# CPU_v3_0.net
KiCad netlist of a schematic drawn in EAGLE
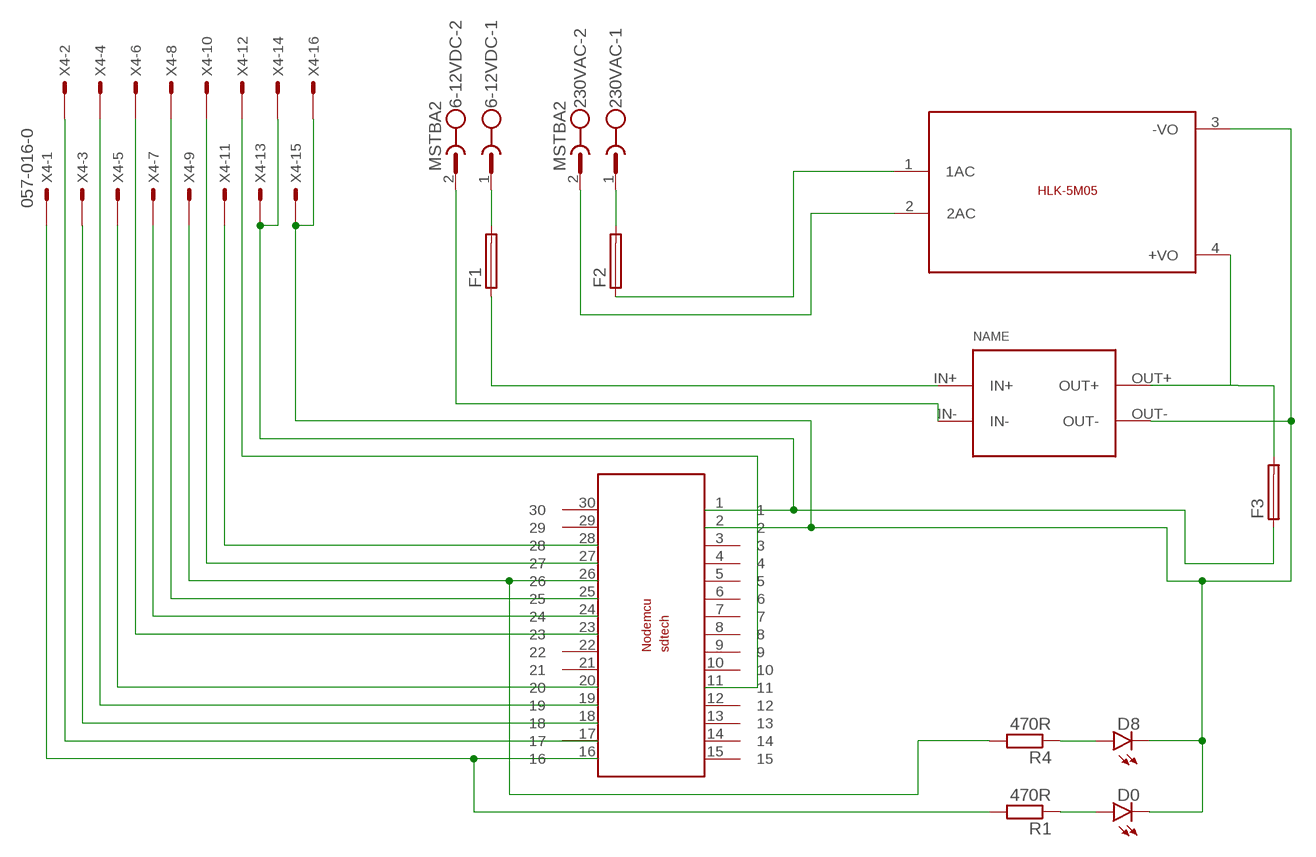
[diagram p0: schematic, sheet 1]

(export (version "E")
  (design (tool "Eeschema 10.0.6"))
  (components
    (comp (ref "6-12VDC")
      (value "MSTBA2")
      (footprint "eagle-import:MSTBA2")
      (fields (field (name "MF") "FARNELL") (field (name "MPN") "1757242"))
      (libsource (lib "eagle-import") (part "MSTBA2"))
    )
    (comp (ref "230VAC")
      (value "MSTBA2")
      (footprint "eagle-import:MSTBA2")
      (fields (field (name "MF") "FARNELL") (field (name "MPN") "1757242"))
      (libsource (lib "eagle-import") (part "MSTBA2"))
    )
    (comp (ref "D0")
      (value "LED3MM")
      (footprint "eagle-import:LED3MM")
      (libsource (lib "eagle-import") (part "LED3MM"))
    )
    (comp (ref "D8")
      (value "LED3MM")
      (footprint "eagle-import:LED3MM")
      (libsource (lib "eagle-import") (part "LED3MM"))
    )
    (comp (ref "F1")
      (value "SH22,5A")
      (footprint "eagle-import:SH22,5A")
      (fields (field (name "MPN") "0031.7701.11"))
      (libsource (lib "eagle-import") (part "SH22,5A"))
    )
    (comp (ref "F2")
      (value "SH22,5A")
      (footprint "eagle-import:SH22,5A")
      (fields (field (name "MPN") "0031.7701.11"))
      (libsource (lib "eagle-import") (part "SH22,5A"))
    )
    (comp (ref "F3")
      (value "SH22,5A")
      (footprint "eagle-import:SH22,5A")
      (fields (field (name "MPN") "0031.7701.11"))
      (libsource (lib "eagle-import") (part "SH22,5A"))
    )
    (comp (ref "R1")
      (value "470R")
      (footprint "eagle-import:0309_10")
      (libsource (lib "eagle-import") (part "R-EU_0309/10"))
    )
    (comp (ref "R4")
      (value "470R")
      (footprint "eagle-import:0309_10")
      (libsource (lib "eagle-import") (part "R-EU_0309/10"))
    )
    (comp (ref "U$1")
      (value "NODEMCUESP8266")
      (footprint "eagle-import:NODEMCUESP8266")
      (fields (field (name "SPICEPREFIX") "X"))
      (libsource (lib "eagle-import") (part "NODEMCUESP8266"))
    )
    (comp (ref "U$2")
      (value "CP8-ADJ")
      (footprint "eagle-import:CP8-ADJ")
      (libsource (lib "eagle-import") (part "CP8-ADJ"))
    )
    (comp (ref "U$3")
      (value "5VDC/5W")
      (footprint "eagle-import:HLK-5M05")
      (libsource (lib "eagle-import") (part "HLK-5M05"))
    )
    (comp (ref "X4")
      (value "057-016-0")
      (footprint "eagle-import:057-016-0")
      (libsource (lib "eagle-import") (part "057-016-0"))
    )
  )
  (nets
    (net (code "1") (name "Net-(6-12VDC-Pad1)") (class "Default")
      (node (ref "6-12VDC") (pin "1") (pinfunction "1_1") (pintype "passive"))
      (node (ref "F1") (pin "2") (pinfunction "2_2") (pintype "passive"))
    )
    (net (code "2") (name "Net-(6-12VDCB-1)") (class "Default")
      (node (ref "6-12VDC") (pin "2") (pinfunction "1_2") (pintype "passive"))
      (node (ref "U$2") (pin "IN-") (pinfunction "IN-_IN-") (pintype "passive"))
    )
    (net (code "3") (name "Net-(230VAC-Pad1)") (class "Default")
      (node (ref "230VAC") (pin "1") (pinfunction "1_1") (pintype "passive"))
      (node (ref "F2") (pin "2") (pinfunction "2_2") (pintype "passive"))
    )
    (net (code "4") (name "Net-(230VACB-1)") (class "Default")
      (node (ref "230VAC") (pin "2") (pinfunction "1_2") (pintype "passive"))
      (node (ref "U$3") (pin "2") (pinfunction "2AC_2") (pintype "bidirectional"))
    )
    (net (code "5") (name "Net-(D0-C)") (class "Default")
      (node (ref "D0") (pin "K") (pinfunction "C_K") (pintype "passive"))
      (node (ref "D8") (pin "K") (pinfunction "C_K") (pintype "passive"))
      (node (ref "U$1") (pin "2") (pinfunction "2_2") (pintype "bidirectional"))
      (node (ref "U$2") (pin "OUT-") (pinfunction "OUT-_OUT-") (pintype "passive"))
      (node (ref "U$3") (pin "3") (pinfunction "-VO_3") (pintype "bidirectional"))
      (node (ref "X4") (pin "15") (pinfunction "S_15") (pintype "passive"))
      (node (ref "X4") (pin "16") (pinfunction "S_16") (pintype "passive"))
    )
    (net (code "6") (name "Net-(D0-PadA)") (class "Default")
      (node (ref "D0") (pin "A") (pinfunction "A_A") (pintype "passive"))
      (node (ref "R1") (pin "1") (pinfunction "1_1") (pintype "passive"))
    )
    (net (code "7") (name "Net-(D8-PadA)") (class "Default")
      (node (ref "D8") (pin "A") (pinfunction "A_A") (pintype "passive"))
      (node (ref "R4") (pin "1") (pinfunction "1_1") (pintype "passive"))
    )
    (net (code "8") (name "Net-(F1-Pad1)") (class "Default")
      (node (ref "F1") (pin "1") (pinfunction "1_1") (pintype "passive"))
      (node (ref "U$2") (pin "IN+") (pinfunction "IN+_IN+") (pintype "passive"))
    )
    (net (code "9") (name "Net-(U$3-+VO)") (class "Default")
      (node (ref "F3") (pin "2") (pinfunction "2_2") (pintype "passive"))
      (node (ref "U$2") (pin "OUT+") (pinfunction "OUT+_OUT+") (pintype "passive"))
      (node (ref "U$3") (pin "4") (pinfunction "+VO_4") (pintype "bidirectional"))
    )
    (net (code "10") (name "Net-(U$3-1AC)") (class "Default")
      (node (ref "F2") (pin "1") (pinfunction "1_1") (pintype "passive"))
      (node (ref "U$3") (pin "1") (pinfunction "1AC_1") (pintype "bidirectional"))
    )
    (net (code "11") (name "Net-(X4A-S)") (class "Default")
      (node (ref "R1") (pin "2") (pinfunction "2_2") (pintype "passive"))
      (node (ref "U$1") (pin "16") (pinfunction "16_16") (pintype "bidirectional"))
      (node (ref "X4") (pin "1") (pinfunction "S_1") (pintype "passive"))
    )
    (net (code "12") (name "Net-(X4B-S)") (class "Default")
      (node (ref "U$1") (pin "27") (pinfunction "27_27") (pintype "bidirectional"))
      (node (ref "X4") (pin "10") (pinfunction "S_10") (pintype "passive"))
    )
    (net (code "13") (name "Net-(X4C-S)") (class "Default")
      (node (ref "U$1") (pin "28") (pinfunction "28_28") (pintype "bidirectional"))
      (node (ref "X4") (pin "11") (pinfunction "S_11") (pintype "passive"))
    )
    (net (code "14") (name "Net-(X4D-S)") (class "Default")
      (node (ref "U$1") (pin "11") (pinfunction "11_11") (pintype "bidirectional"))
      (node (ref "X4") (pin "12") (pinfunction "S_12") (pintype "passive"))
    )
    (net (code "15") (name "Net-(X4E-S)") (class "Default")
      (node (ref "F3") (pin "1") (pinfunction "1_1") (pintype "passive"))
      (node (ref "U$1") (pin "1") (pinfunction "1_1") (pintype "bidirectional"))
      (node (ref "X4") (pin "13") (pinfunction "S_13") (pintype "passive"))
      (node (ref "X4") (pin "14") (pinfunction "S_14") (pintype "passive"))
    )
    (net (code "16") (name "Net-(X4I-S)") (class "Default")
      (node (ref "U$1") (pin "17") (pinfunction "17_17") (pintype "bidirectional"))
      (node (ref "X4") (pin "2") (pinfunction "S_2") (pintype "passive"))
    )
    (net (code "17") (name "Net-(X4J-S)") (class "Default")
      (node (ref "U$1") (pin "18") (pinfunction "18_18") (pintype "bidirectional"))
      (node (ref "X4") (pin "3") (pinfunction "S_3") (pintype "passive"))
    )
    (net (code "18") (name "Net-(X4K-S)") (class "Default")
      (node (ref "U$1") (pin "19") (pinfunction "19_19") (pintype "bidirectional"))
      (node (ref "X4") (pin "4") (pinfunction "S_4") (pintype "passive"))
    )
    (net (code "19") (name "Net-(X4L-S)") (class "Default")
      (node (ref "U$1") (pin "20") (pinfunction "20_20") (pintype "bidirectional"))
      (node (ref "X4") (pin "5") (pinfunction "S_5") (pintype "passive"))
    )
    (net (code "20") (name "Net-(X4M-S)") (class "Default")
      (node (ref "U$1") (pin "23") (pinfunction "23_23") (pintype "bidirectional"))
      (node (ref "X4") (pin "6") (pinfunction "S_6") (pintype "passive"))
    )
    (net (code "21") (name "Net-(X4N-S)") (class "Default")
      (node (ref "U$1") (pin "24") (pinfunction "24_24") (pintype "bidirectional"))
      (node (ref "X4") (pin "7") (pinfunction "S_7") (pintype "passive"))
    )
    (net (code "22") (name "Net-(X4O-S)") (class "Default")
      (node (ref "U$1") (pin "25") (pinfunction "25_25") (pintype "bidirectional"))
      (node (ref "X4") (pin "8") (pinfunction "S_8") (pintype "passive"))
    )
    (net (code "23") (name "Net-(X4P-S)") (class "Default")
      (node (ref "R4") (pin "2") (pinfunction "2_2") (pintype "passive"))
      (node (ref "U$1") (pin "26") (pinfunction "26_26") (pintype "bidirectional"))
      (node (ref "X4") (pin "9") (pinfunction "S_9") (pintype "passive"))
    )
    (net (code "24") (name "unconnected-(U$1-Pad3)") (class "Default")
      (node (ref "U$1") (pin "3") (pinfunction "3_3") (pintype "bidirectional"))
    )
    (net (code "25") (name "unconnected-(U$1-Pad4)") (class "Default")
      (node (ref "U$1") (pin "4") (pinfunction "4_4") (pintype "bidirectional"))
    )
    (net (code "26") (name "unconnected-(U$1-Pad5)") (class "Default")
      (node (ref "U$1") (pin "5") (pinfunction "5_5") (pintype "bidirectional"))
    )
    (net (code "27") (name "unconnected-(U$1-Pad6)") (class "Default")
      (node (ref "U$1") (pin "6") (pinfunction "6_6") (pintype "bidirectional"))
    )
    (net (code "28") (name "unconnected-(U$1-Pad7)") (class "Default")
      (node (ref "U$1") (pin "7") (pinfunction "7_7") (pintype "bidirectional"))
    )
    (net (code "29") (name "unconnected-(U$1-Pad8)") (class "Default")
      (node (ref "U$1") (pin "8") (pinfunction "8_8") (pintype "bidirectional"))
    )
    (net (code "30") (name "unconnected-(U$1-Pad9)") (class "Default")
      (node (ref "U$1") (pin "9") (pinfunction "9_9") (pintype "bidirectional"))
    )
    (net (code "31") (name "unconnected-(U$1-Pad10)") (class "Default")
      (node (ref "U$1") (pin "10") (pinfunction "10_10") (pintype "bidirectional"))
    )
    (net (code "32") (name "unconnected-(U$1-Pad12)") (class "Default")
      (node (ref "U$1") (pin "12") (pinfunction "12_12") (pintype "bidirectional"))
    )
    (net (code "33") (name "unconnected-(U$1-Pad13)") (class "Default")
      (node (ref "U$1") (pin "13") (pinfunction "13_13") (pintype "bidirectional"))
    )
    (net (code "34") (name "unconnected-(U$1-Pad14)") (class "Default")
      (node (ref "U$1") (pin "14") (pinfunction "14_14") (pintype "bidirectional"))
    )
    (net (code "35") (name "unconnected-(U$1-Pad15)") (class "Default")
      (node (ref "U$1") (pin "15") (pinfunction "15_15") (pintype "bidirectional"))
    )
    (net (code "36") (name "unconnected-(U$1-Pad21)") (class "Default")
      (node (ref "U$1") (pin "21") (pinfunction "21_21") (pintype "bidirectional"))
    )
    (net (code "37") (name "unconnected-(U$1-Pad22)") (class "Default")
      (node (ref "U$1") (pin "22") (pinfunction "22_22") (pintype "bidirectional"))
    )
    (net (code "38") (name "unconnected-(U$1-Pad29)") (class "Default")
      (node (ref "U$1") (pin "29") (pinfunction "29_29") (pintype "bidirectional"))
    )
    (net (code "39") (name "unconnected-(U$1-Pad30)") (class "Default")
      (node (ref "U$1") (pin "30") (pinfunction "30_30") (pintype "bidirectional"))
    )
  )
)
